# Sound_Activation_2019.net
KiCad netlist of a schematic drawn in EAGLE
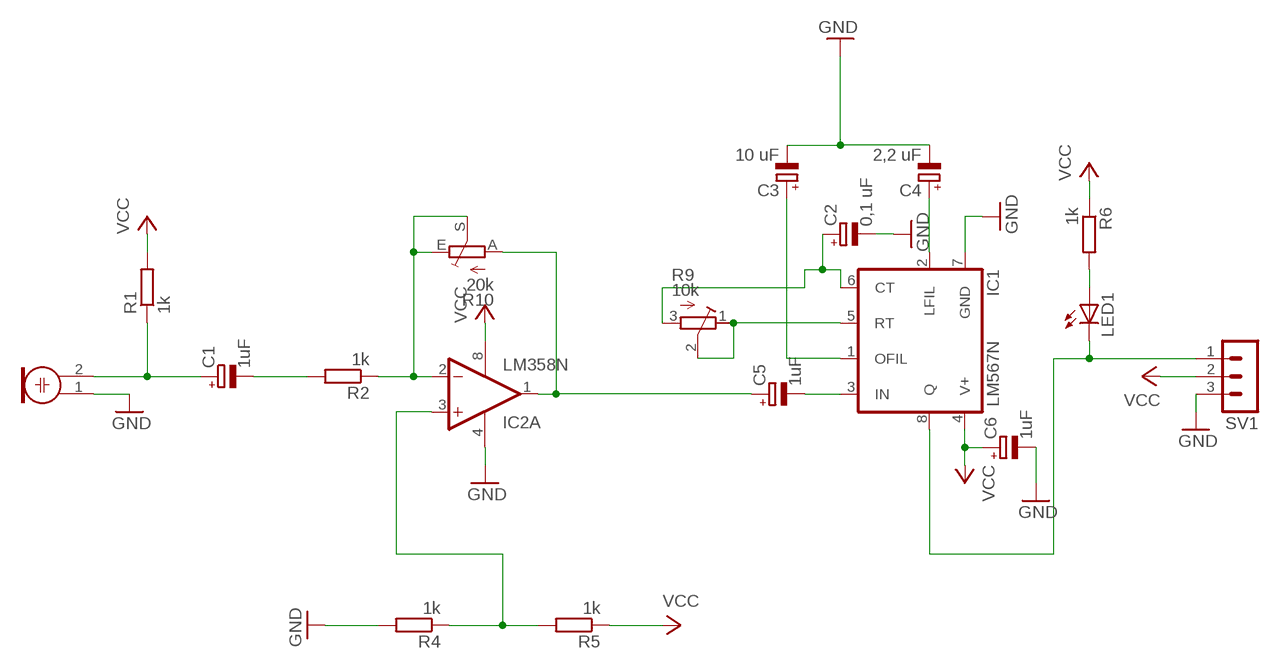
[diagram p0: schematic, sheet 1]

(export (version "E")
  (design (tool "Eeschema 10.0.6"))
  (components
    (comp (ref "C1")
      (value "1uF")
      (footprint "eagle-import:E1,8-4")
      (libsource (lib "eagle-import") (part "CPOL-EUE1.8-4"))
    )
    (comp (ref "C2")
      (value "0,1 uF")
      (footprint "eagle-import:E1,8-4")
      (libsource (lib "eagle-import") (part "CPOL-EUE1.8-4"))
    )
    (comp (ref "C3")
      (value "10 uF")
      (footprint "eagle-import:E1,8-4")
      (libsource (lib "eagle-import") (part "CPOL-EUE1.8-4"))
    )
    (comp (ref "C4")
      (value "2,2 uF")
      (footprint "eagle-import:E1,8-4")
      (libsource (lib "eagle-import") (part "CPOL-EUE1.8-4"))
    )
    (comp (ref "C5")
      (value "1uF")
      (footprint "eagle-import:E1,8-4")
      (libsource (lib "eagle-import") (part "CPOL-EUE1.8-4"))
    )
    (comp (ref "C6")
      (value "1uF")
      (footprint "eagle-import:E1,8-4")
      (libsource (lib "eagle-import") (part "CPOL-EUE1.8-4"))
    )
    (comp (ref "IC1")
      (value "LM567N")
      (footprint "eagle-import:DIL08")
      (libsource (lib "eagle-import") (part "567NLM"))
    )
    (comp (ref "IC2")
      (value "LM358N")
      (footprint "eagle-import:DIL08")
      (libsource (lib "eagle-import") (part "LM358N"))
    )
    (comp (ref "LED1")
      (value "LED3MM")
      (footprint "eagle-import:LED3MM")
      (libsource (lib "eagle-import") (part "LED3MM"))
    )
    (comp (ref "M1")
      (value "ELECTRET_MICROPHON-F6050AP")
      (footprint "eagle-import:F6050AP")
      (libsource (lib "eagle-import") (part "ELECTRET_MICROPHON-F6050AP"))
    )
    (comp (ref "R1")
      (value "1k")
      (footprint "eagle-import:0204_7")
      (libsource (lib "eagle-import") (part "R-EU_0204/7"))
    )
    (comp (ref "R2")
      (value "1k")
      (footprint "eagle-import:0204_7")
      (libsource (lib "eagle-import") (part "R-EU_0204/7"))
    )
    (comp (ref "R4")
      (value "1k")
      (footprint "eagle-import:0204_7")
      (libsource (lib "eagle-import") (part "R-EU_0204/7"))
    )
    (comp (ref "R5")
      (value "1k")
      (footprint "eagle-import:0204_7")
      (libsource (lib "eagle-import") (part "R-EU_0204/7"))
    )
    (comp (ref "R6")
      (value "1k")
      (footprint "eagle-import:0204_7")
      (libsource (lib "eagle-import") (part "R-EU_0204/7"))
    )
    (comp (ref "R9")
      (value "10k")
      (footprint "eagle-import:RTRIM3006P")
      (libsource (lib "eagle-import") (part "R-TRIMM3006P"))
    )
    (comp (ref "R10")
      (value "20k")
      (footprint "eagle-import:CA6V")
      (libsource (lib "eagle-import") (part "TRIM_EU-CA6V"))
    )
    (comp (ref "SV1")
      (value "MA03-1")
      (footprint "eagle-import:MA03-1")
      (libsource (lib "eagle-import") (part "MA03-1"))
    )
  )
  (nets
    (net (code "1") (name "GND") (class "Default")
      (node (ref "C2") (pin "-") (pinfunction "-_-") (pintype "passive"))
      (node (ref "C3") (pin "-") (pinfunction "-_-") (pintype "passive"))
      (node (ref "C4") (pin "-") (pinfunction "-_-") (pintype "passive"))
      (node (ref "C6") (pin "-") (pinfunction "-_-") (pintype "passive"))
      (node (ref "IC1") (pin "7") (pinfunction "GND_7") (pintype "power_in"))
      (node (ref "IC2") (pin "4") (pinfunction "V-_4") (pintype "power_in"))
      (node (ref "M1") (pin "1") (pinfunction "1_1") (pintype "passive"))
      (node (ref "R4") (pin "2") (pinfunction "2_2") (pintype "passive"))
      (node (ref "SV1") (pin "3") (pinfunction "3_3") (pintype "passive"))
    )
    (net (code "2") (name "Net-(C1-Pad+)") (class "Default")
      (node (ref "C1") (pin "+") (pinfunction "+_+") (pintype "passive"))
      (node (ref "M1") (pin "2") (pinfunction "2_2") (pintype "passive"))
      (node (ref "R1") (pin "1") (pinfunction "1_1") (pintype "passive"))
    )
    (net (code "3") (name "Net-(C1-Pad-)") (class "Default")
      (node (ref "C1") (pin "-") (pinfunction "-_-") (pintype "passive"))
      (node (ref "R2") (pin "2") (pinfunction "2_2") (pintype "passive"))
    )
    (net (code "4") (name "Net-(IC1-CT)") (class "Default")
      (node (ref "C2") (pin "+") (pinfunction "+_+") (pintype "passive"))
      (node (ref "IC1") (pin "6") (pinfunction "CT_6") (pintype "passive"))
      (node (ref "R9") (pin "3") (pinfunction "A_3") (pintype "passive"))
    )
    (net (code "5") (name "Net-(IC1-IN)") (class "Default")
      (node (ref "C5") (pin "-") (pinfunction "-_-") (pintype "passive"))
      (node (ref "IC1") (pin "3") (pinfunction "IN_3") (pintype "input"))
    )
    (net (code "6") (name "Net-(IC1-LFIL)") (class "Default")
      (node (ref "C4") (pin "+") (pinfunction "+_+") (pintype "passive"))
      (node (ref "IC1") (pin "2") (pinfunction "LFIL_2") (pintype "passive"))
    )
    (net (code "7") (name "Net-(IC1-OFIL)") (class "Default")
      (node (ref "C3") (pin "+") (pinfunction "+_+") (pintype "passive"))
      (node (ref "IC1") (pin "1") (pinfunction "OFIL_1") (pintype "output"))
    )
    (net (code "8") (name "Net-(IC1-Q)") (class "Default")
      (node (ref "IC1") (pin "8") (pinfunction "Q_8") (pintype "output"))
      (node (ref "LED1") (pin "K") (pinfunction "C_K") (pintype "passive"))
      (node (ref "SV1") (pin "1") (pinfunction "1_1") (pintype "passive"))
    )
    (net (code "9") (name "Net-(IC1-RT)") (class "Default")
      (node (ref "IC1") (pin "5") (pinfunction "RT_5") (pintype "passive"))
      (node (ref "R9") (pin "1") (pinfunction "E_1") (pintype "passive"))
      (node (ref "R9") (pin "2") (pinfunction "S_2") (pintype "passive"))
    )
    (net (code "10") (name "Net-(IC2A-+IN)") (class "Default")
      (node (ref "IC2") (pin "3") (pinfunction "+IN_3") (pintype "input"))
      (node (ref "R4") (pin "1") (pinfunction "1_1") (pintype "passive"))
      (node (ref "R5") (pin "2") (pinfunction "2_2") (pintype "passive"))
    )
    (net (code "11") (name "Net-(IC2A--IN)") (class "Default")
      (node (ref "IC2") (pin "2") (pinfunction "-IN_2") (pintype "input"))
      (node (ref "R10") (pin "E") (pinfunction "E_E") (pintype "passive"))
      (node (ref "R10") (pin "S") (pinfunction "S_S") (pintype "passive"))
      (node (ref "R2") (pin "1") (pinfunction "1_1") (pintype "passive"))
    )
    (net (code "12") (name "Net-(IC2A-OUT)") (class "Default")
      (node (ref "C5") (pin "+") (pinfunction "+_+") (pintype "passive"))
      (node (ref "IC2") (pin "1") (pinfunction "OUT_1") (pintype "output"))
      (node (ref "R10") (pin "A") (pinfunction "A_A") (pintype "passive"))
    )
    (net (code "13") (name "Net-(LED1-PadA)") (class "Default")
      (node (ref "LED1") (pin "A") (pinfunction "A_A") (pintype "passive"))
      (node (ref "R6") (pin "2") (pinfunction "2_2") (pintype "passive"))
    )
    (net (code "14") (name "VCC") (class "Default")
      (node (ref "C6") (pin "+") (pinfunction "+_+") (pintype "passive"))
      (node (ref "IC1") (pin "4") (pinfunction "V+_4") (pintype "power_in"))
      (node (ref "IC2") (pin "8") (pinfunction "V+_8") (pintype "power_in"))
      (node (ref "R1") (pin "2") (pinfunction "2_2") (pintype "passive"))
      (node (ref "R5") (pin "1") (pinfunction "1_1") (pintype "passive"))
      (node (ref "R6") (pin "1") (pinfunction "1_1") (pintype "passive"))
      (node (ref "SV1") (pin "2") (pinfunction "2_2") (pintype "passive"))
    )
  )
)
